# sbattery.net
KiCad netlist of a schematic drawn in Altium Designer
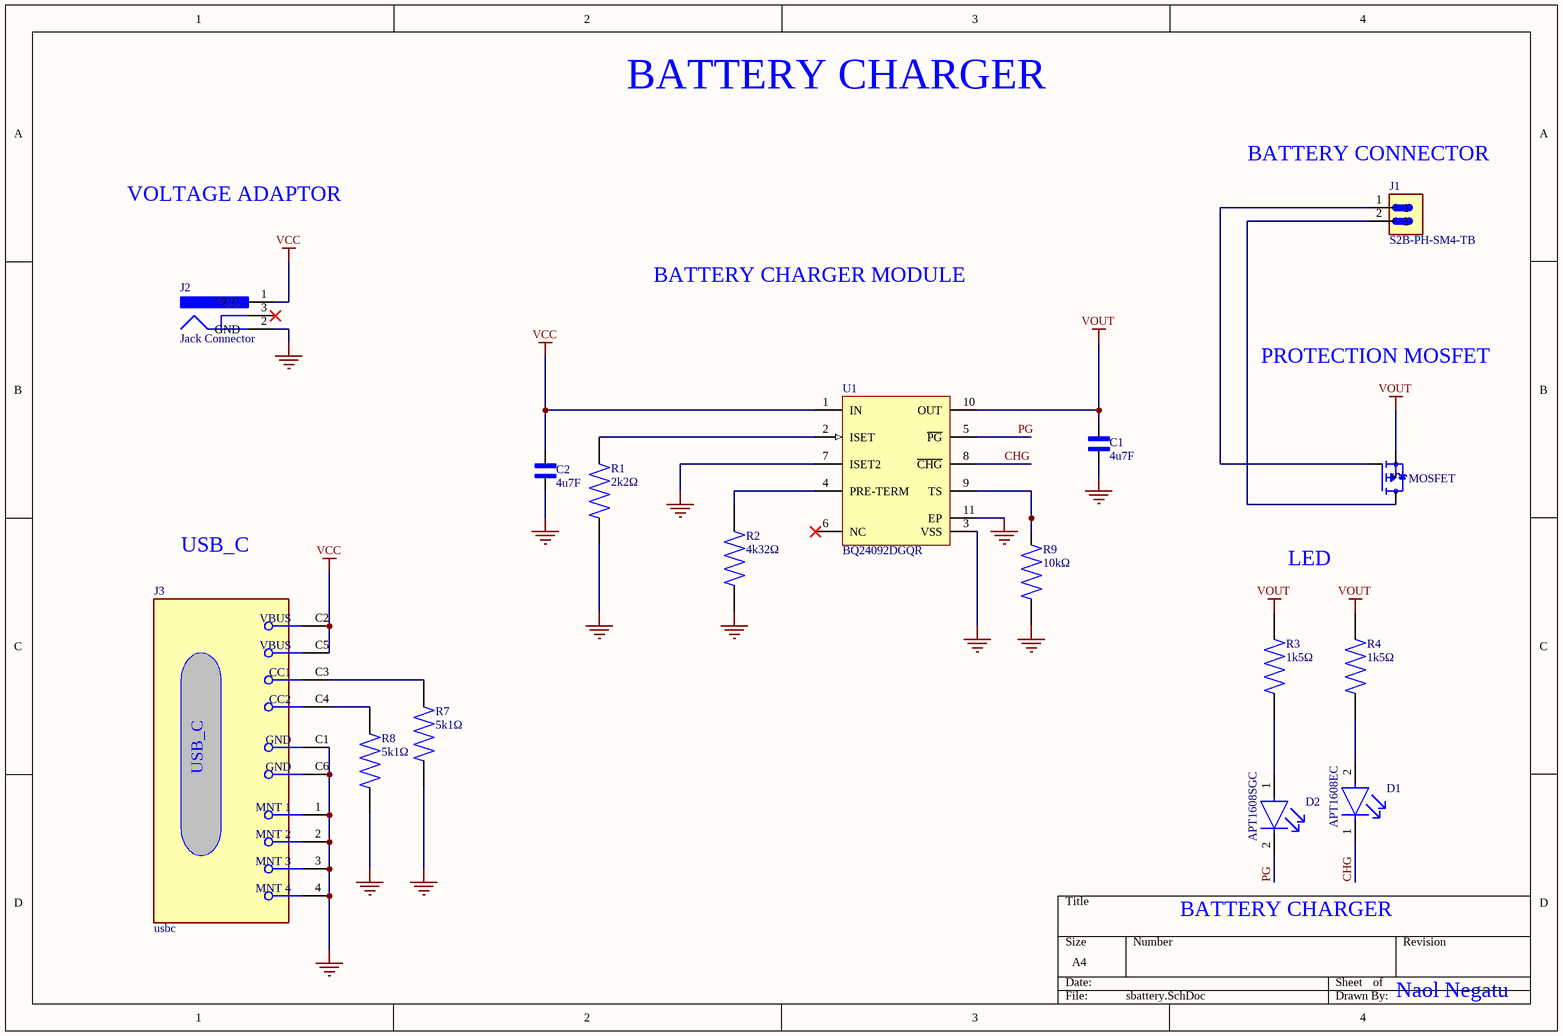
[diagram p0: sbattery.SchDoc]

(export (version "E")
  (design (tool "Eeschema 10.0.6"))
  (components
    (comp (ref "C1")
      (value "4u7F")
      (footprint "CAPC2012X88N")
      (description "Ceramic Capacitor, Ceramic, 16V, 10% +Tol, 10% -Tol, X7R, 0.15 TC, 4.7uF, Surface Mount, 0805")
      (fields
        (field (name "MANUFACTURER") "Yageo Group")
        (field (name "MANUFACTURER PART NUMBER") "CC0805KFX7R7BB475")
      )
      (libsource (lib "sbattery") (part "CC0805KFX7R7BB475"))
    )
    (comp (ref "C2")
      (value "4u7F")
      (footprint "CAPC2012X88N")
      (description "Ceramic Capacitor, Ceramic, 16V, 10% +Tol, 10% -Tol, X7R, 0.15 TC, 4.7uF, Surface Mount, 0805")
      (fields
        (field (name "MANUFACTURER") "Yageo Group")
        (field (name "MANUFACTURER PART NUMBER") "CC0805KFX7R7BB475")
      )
      (libsource (lib "sbattery") (part "CC0805KFX7R7BB475"))
    )
    (comp (ref "D1")
      (value "APT1608EC")
      (footprint "FP-APT1608EC-MFG")
      (description "1.6X0.8 MM SMD CHIP LED LAMP Single Color LED, High Efficiency Red, Water Clear, 1.2mm")
      (fields (field (name "MANUFACTURER") "Kingbright") (field (name "LCSC PART#") "C5554143"))
      (libsource (lib "sbattery") (part "APT1608EC"))
    )
    (comp (ref "D2")
      (value "APT1608SGC")
      (footprint "FP-APT2012MGC-MFG")
      (description "LED High-Power Uni-Color Super Bright Green 565nm 2.2V 2-Pin Chip LED T/R")
      (fields (field (name "MANUFACTURER") "Kingbright") (field (name "LCSC PART#") "C5875754"))
      (libsource (lib "sbattery") (part "APT1608SGC"))
    )
    (comp (ref "J1")
      (value "S2B-PH-SM4-TB")
      (footprint "JST_S2B-PH-SM4-TB")
      (description "Board Connector, 2 Contact(s), 1 Row(s), Male, Right Angle, Surface Mount Terminal")
      (fields (field (name "MANUFACTURER") "JST"))
      (libsource (lib "sbattery") (part "S2B-PH-SM4-TB"))
    )
    (comp (ref "J2")
      (value "Jack Connector")
      (footprint "CUI_PJ-002AH-SMT-TR")
      (description "2.0 x 6.5 mm, 5.0 A, Horizontal, Surface Mount (SMT), Dc Power Jack Connector")
      (fields
        (field (name "MANUFACTURER") "Same Sky")
        (field (name "MANUFACTURER PART NUMBER") "PJ-002AH-SMT-TR")
      )
      (libsource (lib "sbattery") (part "PJ-002AH-SMT-TR"))
    )
    (comp (ref "J3")
      (value "usbc")
      (footprint "FP-217176-0001-MFG")
      (description "USB Connector, Receptacle, USB 2.0, USB Type C, 6 Ways, Gold, SMT, Right Angle, Copper Alloy")
      (fields (field (name "MANUFACTURER") "Molex") (field (name "MANUFACTURER PART NUMBER") "217176-0001"))
      (libsource (lib "sbattery") (part "217176-0001"))
    )
    (comp (ref "MOSFET")
      (value "P CHANNEL")
      (footprint "SOT23-3")
      (description "Transistor: P-MOSFET; unipolar; -30V; 4, 2A; 1, 4W; 85 mOhm; ; -55+150 st.C; SMD; SOT23")
      (fields
        (field (name "MANUFACTURER") "Alpha & Omega Semiconductor")
        (field (name "MANUFACTURER PART NUMBER") "AO3401A")
      )
      (libsource (lib "sbattery") (part "AO3401A"))
    )
    (comp (ref "R1")
      (value "2k2Ω")
      (footprint "RESC2012X60N")
      (description "125Mw Thick Film Resistors 100Ppm/ 1% 2.2K 0805 Chip Resistor Surface Mount Rohs")
      (fields
        (field (name "MANUFACTURER") "Yageo Group")
        (field (name "MANUFACTURER PART NUMBER") "RC0805FR-072K2L")
      )
      (libsource (lib "sbattery") (part "RC0805FR-072K2L"))
    )
    (comp (ref "R2")
      (value "4k32Ω")
      (footprint "RESC2012X60N")
      (description "Res Thick Film 0805 4.32K Ohm 1% 0.125W(1/8W) ±100ppm/C Pad SMD T/R")
      (fields
        (field (name "MANUFACTURER") "Yageo Group")
        (field (name "MANUFACTURER PART NUMBER") "RC0805FR-074K32L")
      )
      (libsource (lib "sbattery") (part "RC0805FR-074K32L"))
    )
    (comp (ref "R3")
      (value "1k5Ω")
      (footprint "RESC2012X60N")
      (description "Res Thick Film 0805 1.5K Ohm 5% 0.125W(1/8W) ±100ppm/C Pad SMD T/R")
      (fields
        (field (name "MANUFACTURER") "Yageo Group")
        (field (name "MANUFACTURER PART NUMBER") "RC0805JR-131K5L")
      )
      (libsource (lib "sbattery") (part "RC0805JR-131K5L"))
    )
    (comp (ref "R4")
      (value "1k5Ω")
      (footprint "RESC2012X60N")
      (description "Res Thick Film 0805 1.5K Ohm 5% 0.125W(1/8W) ±100ppm/C Pad SMD T/R")
      (fields
        (field (name "MANUFACTURER") "Yageo Group")
        (field (name "MANUFACTURER PART NUMBER") "RC0805JR-131K5L")
      )
      (libsource (lib "sbattery") (part "RC0805JR-131K5L"))
    )
    (comp (ref "R7")
      (value "5k1Ω")
      (footprint "RESC2012X60N")
      (description "Res Thick Film 0805 5.1K Ohm 1% 0.125W(1/8W) ±100ppm/C Pad SMD T/R")
      (fields
        (field (name "MANUFACTURER") "Yageo Group")
        (field (name "MANUFACTURER PART NUMBER") "RC0805FR-135K1L")
      )
      (libsource (lib "sbattery") (part "RC0805FR-135K1L"))
    )
    (comp (ref "R8")
      (value "5k1Ω")
      (footprint "RESC2012X60N")
      (description "Res Thick Film 0805 5.1K Ohm 1% 0.125W(1/8W) ±100ppm/C Pad SMD T/R")
      (fields
        (field (name "MANUFACTURER") "Yageo Group")
        (field (name "MANUFACTURER PART NUMBER") "RC0805FR-135K1L")
      )
      (libsource (lib "sbattery") (part "RC0805FR-135K1L"))
    )
    (comp (ref "R9")
      (value "10kΩ")
      (footprint "RESC2012X60N")
      (description "Res Thick Film 0805 10K Ohm 1% 0.125W ±100ppm/°C Molded SMD Paper T/R")
      (fields
        (field (name "MANUFACTURER") "Stackpole Electronics")
        (field (name "MANUFACTURER PART NUMBER") "RMCF0805FT10K0")
      )
      (libsource (lib "sbattery") (part "RMCF0805FT10K0"))
    )
    (comp (ref "U1")
      (value "BQ24092DGQR")
      (footprint "DGQ0010D_L")
      (description "1-cell, 1-A, Li-ion battery charger with operation over JEITA and 10kΩ NTC 10-HVSSOP -40 to 150")
      (fields (field (name "MANUFACTURER") "Texas Instruments") (field (name "LCSC PART#") "C133237"))
      (libsource (lib "sbattery") (part "BQ24092DGQR"))
    )
  )
  (nets
    (net (code "1") (name "/CHG") (class "Default")
      (node (ref "D1") (pin "1") (pinfunction "C_1") (pintype "passive"))
      (node (ref "U1") (pin "8") (pinfunction "~{CHG}_8") (pintype "tri_state"))
    )
    (net (code "2") (name "/PG") (class "Default")
      (node (ref "D2") (pin "2") (pinfunction "C_2") (pintype "passive"))
      (node (ref "U1") (pin "5") (pinfunction "~{PG}_5") (pintype "tri_state"))
    )
    (net (code "3") (name "GND") (class "Default")
      (node (ref "C1") (pin "2") (pinfunction "2_2") (pintype "passive"))
      (node (ref "C2") (pin "2") (pinfunction "2_2") (pintype "passive"))
      (node (ref "J2") (pin "2") (pinfunction "GND_2") (pintype "passive"))
      (node (ref "J3") (pin "1") (pinfunction "MNT_1_1") (pintype "passive"))
      (node (ref "J3") (pin "2") (pinfunction "MNT_2_2") (pintype "passive"))
      (node (ref "J3") (pin "3") (pinfunction "MNT_3_3") (pintype "passive"))
      (node (ref "J3") (pin "4") (pinfunction "MNT_4_4") (pintype "passive"))
      (node (ref "J3") (pin "C1") (pinfunction "GND_C1") (pintype "power_in"))
      (node (ref "J3") (pin "C6") (pinfunction "GND_C6") (pintype "power_in"))
      (node (ref "R1") (pin "1") (pinfunction "1_1") (pintype "passive"))
      (node (ref "R2") (pin "1") (pinfunction "1_1") (pintype "passive"))
      (node (ref "R7") (pin "1") (pinfunction "1_1") (pintype "passive"))
      (node (ref "R8") (pin "1") (pinfunction "1_1") (pintype "passive"))
      (node (ref "R9") (pin "1") (pinfunction "1_1") (pintype "passive"))
      (node (ref "U1") (pin "11") (pinfunction "EP_11") (pintype "power_in"))
      (node (ref "U1") (pin "3") (pinfunction "VSS_3") (pintype "power_in"))
      (node (ref "U1") (pin "7") (pinfunction "ISET2_7") (pintype "passive"))
    )
    (net (code "4") (name "Net-(D1-A)") (class "Default")
      (node (ref "D1") (pin "2") (pinfunction "A_2") (pintype "passive"))
      (node (ref "R4") (pin "1") (pinfunction "1_1") (pintype "passive"))
    )
    (net (code "5") (name "Net-(D2-A)") (class "Default")
      (node (ref "D2") (pin "1") (pinfunction "A_1") (pintype "passive"))
      (node (ref "R3") (pin "1") (pinfunction "1_1") (pintype "passive"))
    )
    (net (code "6") (name "Net-(J3-CC1)") (class "Default")
      (node (ref "J3") (pin "C3") (pinfunction "CC1_C3") (pintype "passive"))
      (node (ref "R7") (pin "2") (pinfunction "2_2") (pintype "passive"))
    )
    (net (code "7") (name "Net-(J3-CC2)") (class "Default")
      (node (ref "J3") (pin "C4") (pinfunction "CC2_C4") (pintype "passive"))
      (node (ref "R8") (pin "2") (pinfunction "2_2") (pintype "passive"))
    )
    (net (code "8") (name "Net-(MOSFET-D)") (class "Default")
      (node (ref "J1") (pin "2") (pinfunction "2_2") (pintype "passive"))
      (node (ref "MOSFET") (pin "3") (pinfunction "D_3") (pintype "passive"))
    )
    (net (code "9") (name "Net-(MOSFET-G)") (class "Default")
      (node (ref "J1") (pin "1") (pinfunction "1_1") (pintype "passive"))
      (node (ref "MOSFET") (pin "1") (pinfunction "G_1") (pintype "passive"))
    )
    (net (code "10") (name "Net-(U1-ISET)") (class "Default")
      (node (ref "R1") (pin "2") (pinfunction "2_2") (pintype "passive"))
      (node (ref "U1") (pin "2") (pinfunction "ISET_2") (pintype "input"))
    )
    (net (code "11") (name "Net-(U1-PRE-TERM)") (class "Default")
      (node (ref "R2") (pin "2") (pinfunction "2_2") (pintype "passive"))
      (node (ref "U1") (pin "4") (pinfunction "PRE-TERM_4") (pintype "passive"))
    )
    (net (code "12") (name "Net-(U1-TS)") (class "Default")
      (node (ref "R9") (pin "2") (pinfunction "2_2") (pintype "passive"))
      (node (ref "U1") (pin "9") (pinfunction "TS_9") (pintype "passive"))
    )
    (net (code "13") (name "VCC") (class "Default")
      (node (ref "C2") (pin "1") (pinfunction "1_1") (pintype "passive"))
      (node (ref "J2") (pin "1") (pinfunction "VCC_1") (pintype "passive"))
      (node (ref "J3") (pin "C2") (pinfunction "VBUS_C2") (pintype "passive"))
      (node (ref "J3") (pin "C5") (pinfunction "VBUS_C5") (pintype "passive"))
      (node (ref "U1") (pin "1") (pinfunction "IN_1") (pintype "power_in"))
    )
    (net (code "14") (name "VOUT") (class "Default")
      (node (ref "C1") (pin "1") (pinfunction "1_1") (pintype "passive"))
      (node (ref "MOSFET") (pin "2") (pinfunction "S_2") (pintype "passive"))
      (node (ref "R3") (pin "2") (pinfunction "2_2") (pintype "passive"))
      (node (ref "R4") (pin "2") (pinfunction "2_2") (pintype "passive"))
      (node (ref "U1") (pin "10") (pinfunction "OUT_10") (pintype "power_in"))
    )
    (net (code "15") (name "unconnected-(J2-Pad3)") (class "Default")
      (node (ref "J2") (pin "3") (pinfunction "3_3") (pintype "passive+no_connect"))
    )
    (net (code "16") (name "unconnected-(U1-NC-Pad6)") (class "Default")
      (node (ref "U1") (pin "6") (pinfunction "NC_6") (pintype "passive+no_connect"))
    )
  )
)
